# CurrentSenseMXChip.net
KiCad netlist of a schematic drawn in EAGLE
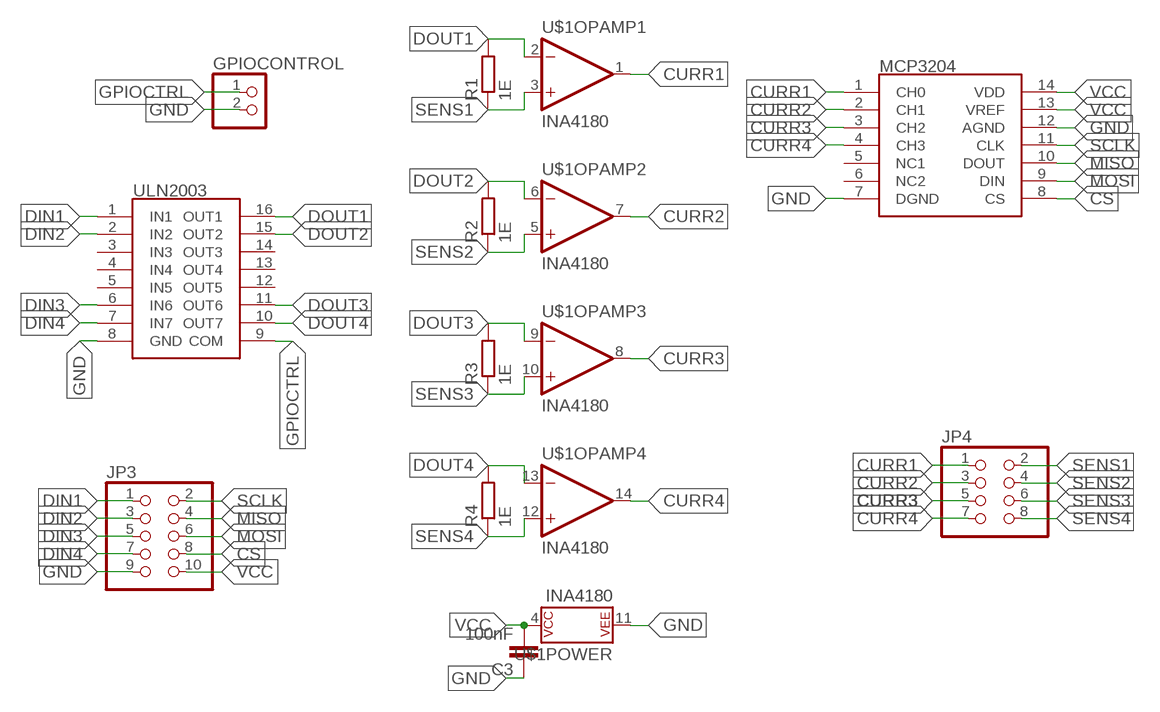
[diagram p0: schematic, sheet 1]

(export (version "E")
  (design (tool "Eeschema 10.0.6"))
  (components
    (comp (ref "C3")
      (value "100nF")
      (footprint "eagle-import:C1206")
      (libsource (lib "eagle-import") (part "C-EUC1206"))
    )
    (comp (ref "GPIOCONTROL")
      (value "PINHD-1X2")
      (footprint "eagle-import:1X02")
      (libsource (lib "eagle-import") (part "PINHD-1X2"))
    )
    (comp (ref "JP3")
      (value "PINHD-2X5")
      (footprint "eagle-import:2X05")
      (libsource (lib "eagle-import") (part "PINHD-2X5"))
    )
    (comp (ref "JP4")
      (value "PINHD-2X4")
      (footprint "eagle-import:2X04")
      (libsource (lib "eagle-import") (part "PINHD-2X4"))
    )
    (comp (ref "R1")
      (value "1E")
      (footprint "eagle-import:R1206")
      (libsource (lib "eagle-import") (part "R-EU_R1206"))
    )
    (comp (ref "R2")
      (value "1E")
      (footprint "eagle-import:R1206")
      (libsource (lib "eagle-import") (part "R-EU_R1206"))
    )
    (comp (ref "R3")
      (value "1E")
      (footprint "eagle-import:R1206")
      (libsource (lib "eagle-import") (part "R-EU_R1206"))
    )
    (comp (ref "R4")
      (value "1E")
      (footprint "eagle-import:R1206")
      (libsource (lib "eagle-import") (part "R-EU_R1206"))
    )
    (comp (ref "U$1")
      (value "INA4180")
      (footprint "eagle-import:TSSOP-14")
      (libsource (lib "eagle-import") (part "INA4180"))
    )
    (comp (ref "U$2")
      (value "ULN2003")
      (footprint "eagle-import:SO16")
      (libsource (lib "eagle-import") (part "ULN2003"))
    )
    (comp (ref "U$3")
      (value "MCP3204")
      (footprint "eagle-import:TSSOP-14")
      (libsource (lib "eagle-import") (part "MCP3204"))
    )
  )
  (nets
    (net (code "1") (name "CS") (class "Default")
      (node (ref "JP3") (pin "8") (pinfunction "8_8") (pintype "passive"))
      (node (ref "U$3") (pin "8") (pinfunction "CS_8") (pintype "bidirectional"))
    )
    (net (code "2") (name "CURR1") (class "Default")
      (node (ref "JP4") (pin "1") (pinfunction "1_1") (pintype "passive"))
      (node (ref "U$1") (pin "1") (pinfunction "OUT_1") (pintype "output"))
      (node (ref "U$3") (pin "1") (pinfunction "CH0_1") (pintype "bidirectional"))
    )
    (net (code "3") (name "CURR2") (class "Default")
      (node (ref "JP4") (pin "3") (pinfunction "3_3") (pintype "passive"))
      (node (ref "U$1") (pin "7") (pinfunction "OUT_7") (pintype "output"))
      (node (ref "U$3") (pin "2") (pinfunction "CH1_2") (pintype "bidirectional"))
    )
    (net (code "4") (name "CURR3") (class "Default")
      (node (ref "JP4") (pin "5") (pinfunction "5_5") (pintype "passive"))
      (node (ref "U$1") (pin "8") (pinfunction "OUT_8") (pintype "output"))
      (node (ref "U$3") (pin "3") (pinfunction "CH2_3") (pintype "bidirectional"))
    )
    (net (code "5") (name "CURR4") (class "Default")
      (node (ref "JP4") (pin "7") (pinfunction "7_7") (pintype "passive"))
      (node (ref "U$1") (pin "14") (pinfunction "OUT_14") (pintype "output"))
      (node (ref "U$3") (pin "4") (pinfunction "CH3_4") (pintype "bidirectional"))
    )
    (net (code "6") (name "DIN1") (class "Default")
      (node (ref "JP3") (pin "1") (pinfunction "1_1") (pintype "passive"))
      (node (ref "U$2") (pin "1") (pinfunction "IN1_1") (pintype "bidirectional"))
    )
    (net (code "7") (name "DIN2") (class "Default")
      (node (ref "JP3") (pin "3") (pinfunction "3_3") (pintype "passive"))
      (node (ref "U$2") (pin "2") (pinfunction "IN2_2") (pintype "bidirectional"))
    )
    (net (code "8") (name "DIN3") (class "Default")
      (node (ref "JP3") (pin "5") (pinfunction "5_5") (pintype "passive"))
      (node (ref "U$2") (pin "6") (pinfunction "IN6_6") (pintype "bidirectional"))
    )
    (net (code "9") (name "DIN4") (class "Default")
      (node (ref "JP3") (pin "7") (pinfunction "7_7") (pintype "passive"))
      (node (ref "U$2") (pin "7") (pinfunction "IN7_7") (pintype "bidirectional"))
    )
    (net (code "10") (name "DOUT1") (class "Default")
      (node (ref "R1") (pin "2") (pinfunction "2_2") (pintype "passive"))
      (node (ref "U$1") (pin "2") (pinfunction "-IN_2") (pintype "input"))
      (node (ref "U$2") (pin "16") (pinfunction "OUT1_16") (pintype "bidirectional"))
    )
    (net (code "11") (name "DOUT2") (class "Default")
      (node (ref "R2") (pin "2") (pinfunction "2_2") (pintype "passive"))
      (node (ref "U$1") (pin "6") (pinfunction "-IN_6") (pintype "input"))
      (node (ref "U$2") (pin "15") (pinfunction "OUT2_15") (pintype "bidirectional"))
    )
    (net (code "12") (name "DOUT3") (class "Default")
      (node (ref "R3") (pin "2") (pinfunction "2_2") (pintype "passive"))
      (node (ref "U$1") (pin "9") (pinfunction "-IN_9") (pintype "input"))
      (node (ref "U$2") (pin "11") (pinfunction "OUT6_11") (pintype "bidirectional"))
    )
    (net (code "13") (name "DOUT4") (class "Default")
      (node (ref "R4") (pin "2") (pinfunction "2_2") (pintype "passive"))
      (node (ref "U$1") (pin "13") (pinfunction "-IN_13") (pintype "input"))
      (node (ref "U$2") (pin "10") (pinfunction "OUT7_10") (pintype "bidirectional"))
    )
    (net (code "14") (name "GND") (class "Default")
      (node (ref "C3") (pin "1") (pinfunction "1_1") (pintype "passive"))
      (node (ref "GPIOCONTROL") (pin "2") (pinfunction "2_2") (pintype "passive"))
      (node (ref "JP3") (pin "9") (pinfunction "9_9") (pintype "passive"))
      (node (ref "U$1") (pin "11") (pinfunction "P$V-_11") (pintype "bidirectional"))
      (node (ref "U$2") (pin "8") (pinfunction "GND_8") (pintype "bidirectional"))
      (node (ref "U$3") (pin "12") (pinfunction "AGND_12") (pintype "bidirectional"))
      (node (ref "U$3") (pin "7") (pinfunction "DGND_7") (pintype "bidirectional"))
    )
    (net (code "15") (name "GPIOCTRL") (class "Default")
      (node (ref "GPIOCONTROL") (pin "1") (pinfunction "1_1") (pintype "passive"))
      (node (ref "U$2") (pin "9") (pinfunction "COM_9") (pintype "bidirectional"))
    )
    (net (code "16") (name "MISO") (class "Default")
      (node (ref "JP3") (pin "4") (pinfunction "4_4") (pintype "passive"))
      (node (ref "U$3") (pin "10") (pinfunction "DOUT_10") (pintype "bidirectional"))
    )
    (net (code "17") (name "MOSI") (class "Default")
      (node (ref "JP3") (pin "6") (pinfunction "6_6") (pintype "passive"))
      (node (ref "U$3") (pin "9") (pinfunction "DIN_9") (pintype "bidirectional"))
    )
    (net (code "18") (name "SCLK") (class "Default")
      (node (ref "JP3") (pin "2") (pinfunction "2_2") (pintype "passive"))
      (node (ref "U$3") (pin "11") (pinfunction "CLK_11") (pintype "bidirectional"))
    )
    (net (code "19") (name "SENS1") (class "Default")
      (node (ref "JP4") (pin "2") (pinfunction "2_2") (pintype "passive"))
      (node (ref "R1") (pin "1") (pinfunction "1_1") (pintype "passive"))
      (node (ref "U$1") (pin "3") (pinfunction "+IN_3") (pintype "input"))
    )
    (net (code "20") (name "SENS2") (class "Default")
      (node (ref "JP4") (pin "4") (pinfunction "4_4") (pintype "passive"))
      (node (ref "R2") (pin "1") (pinfunction "1_1") (pintype "passive"))
      (node (ref "U$1") (pin "5") (pinfunction "+IN_5") (pintype "input"))
    )
    (net (code "21") (name "SENS3") (class "Default")
      (node (ref "JP4") (pin "6") (pinfunction "6_6") (pintype "passive"))
      (node (ref "R3") (pin "1") (pinfunction "1_1") (pintype "passive"))
      (node (ref "U$1") (pin "10") (pinfunction "+IN_10") (pintype "input"))
    )
    (net (code "22") (name "SENS4") (class "Default")
      (node (ref "JP4") (pin "8") (pinfunction "8_8") (pintype "passive"))
      (node (ref "R4") (pin "1") (pinfunction "1_1") (pintype "passive"))
      (node (ref "U$1") (pin "12") (pinfunction "+IN_12") (pintype "input"))
    )
    (net (code "23") (name "VCC") (class "Default")
      (node (ref "C3") (pin "2") (pinfunction "2_2") (pintype "passive"))
      (node (ref "JP3") (pin "10") (pinfunction "10_10") (pintype "passive"))
      (node (ref "U$1") (pin "4") (pinfunction "P$V+_4") (pintype "bidirectional"))
      (node (ref "U$3") (pin "13") (pinfunction "VREF_13") (pintype "bidirectional"))
      (node (ref "U$3") (pin "14") (pinfunction "VDD_14") (pintype "bidirectional"))
    )
    (net (code "24") (name "unconnected-(U$2-IN3-Pad3)") (class "Default")
      (node (ref "U$2") (pin "3") (pinfunction "IN3_3") (pintype "bidirectional"))
    )
    (net (code "25") (name "unconnected-(U$2-IN4-Pad4)") (class "Default")
      (node (ref "U$2") (pin "4") (pinfunction "IN4_4") (pintype "bidirectional"))
    )
    (net (code "26") (name "unconnected-(U$2-IN5-Pad5)") (class "Default")
      (node (ref "U$2") (pin "5") (pinfunction "IN5_5") (pintype "bidirectional"))
    )
    (net (code "27") (name "unconnected-(U$2-OUT3-Pad14)") (class "Default")
      (node (ref "U$2") (pin "14") (pinfunction "OUT3_14") (pintype "bidirectional"))
    )
    (net (code "28") (name "unconnected-(U$2-OUT4-Pad13)") (class "Default")
      (node (ref "U$2") (pin "13") (pinfunction "OUT4_13") (pintype "bidirectional"))
    )
    (net (code "29") (name "unconnected-(U$2-OUT5-Pad12)") (class "Default")
      (node (ref "U$2") (pin "12") (pinfunction "OUT5_12") (pintype "bidirectional"))
    )
    (net (code "30") (name "unconnected-(U$3-NC1-Pad5)") (class "Default")
      (node (ref "U$3") (pin "5") (pinfunction "NC1_5") (pintype "bidirectional"))
    )
    (net (code "31") (name "unconnected-(U$3-NC2-Pad6)") (class "Default")
      (node (ref "U$3") (pin "6") (pinfunction "NC2_6") (pintype "bidirectional"))
    )
  )
)
